# PiZeroAudio.net
KiCad netlist of a schematic drawn in EAGLE
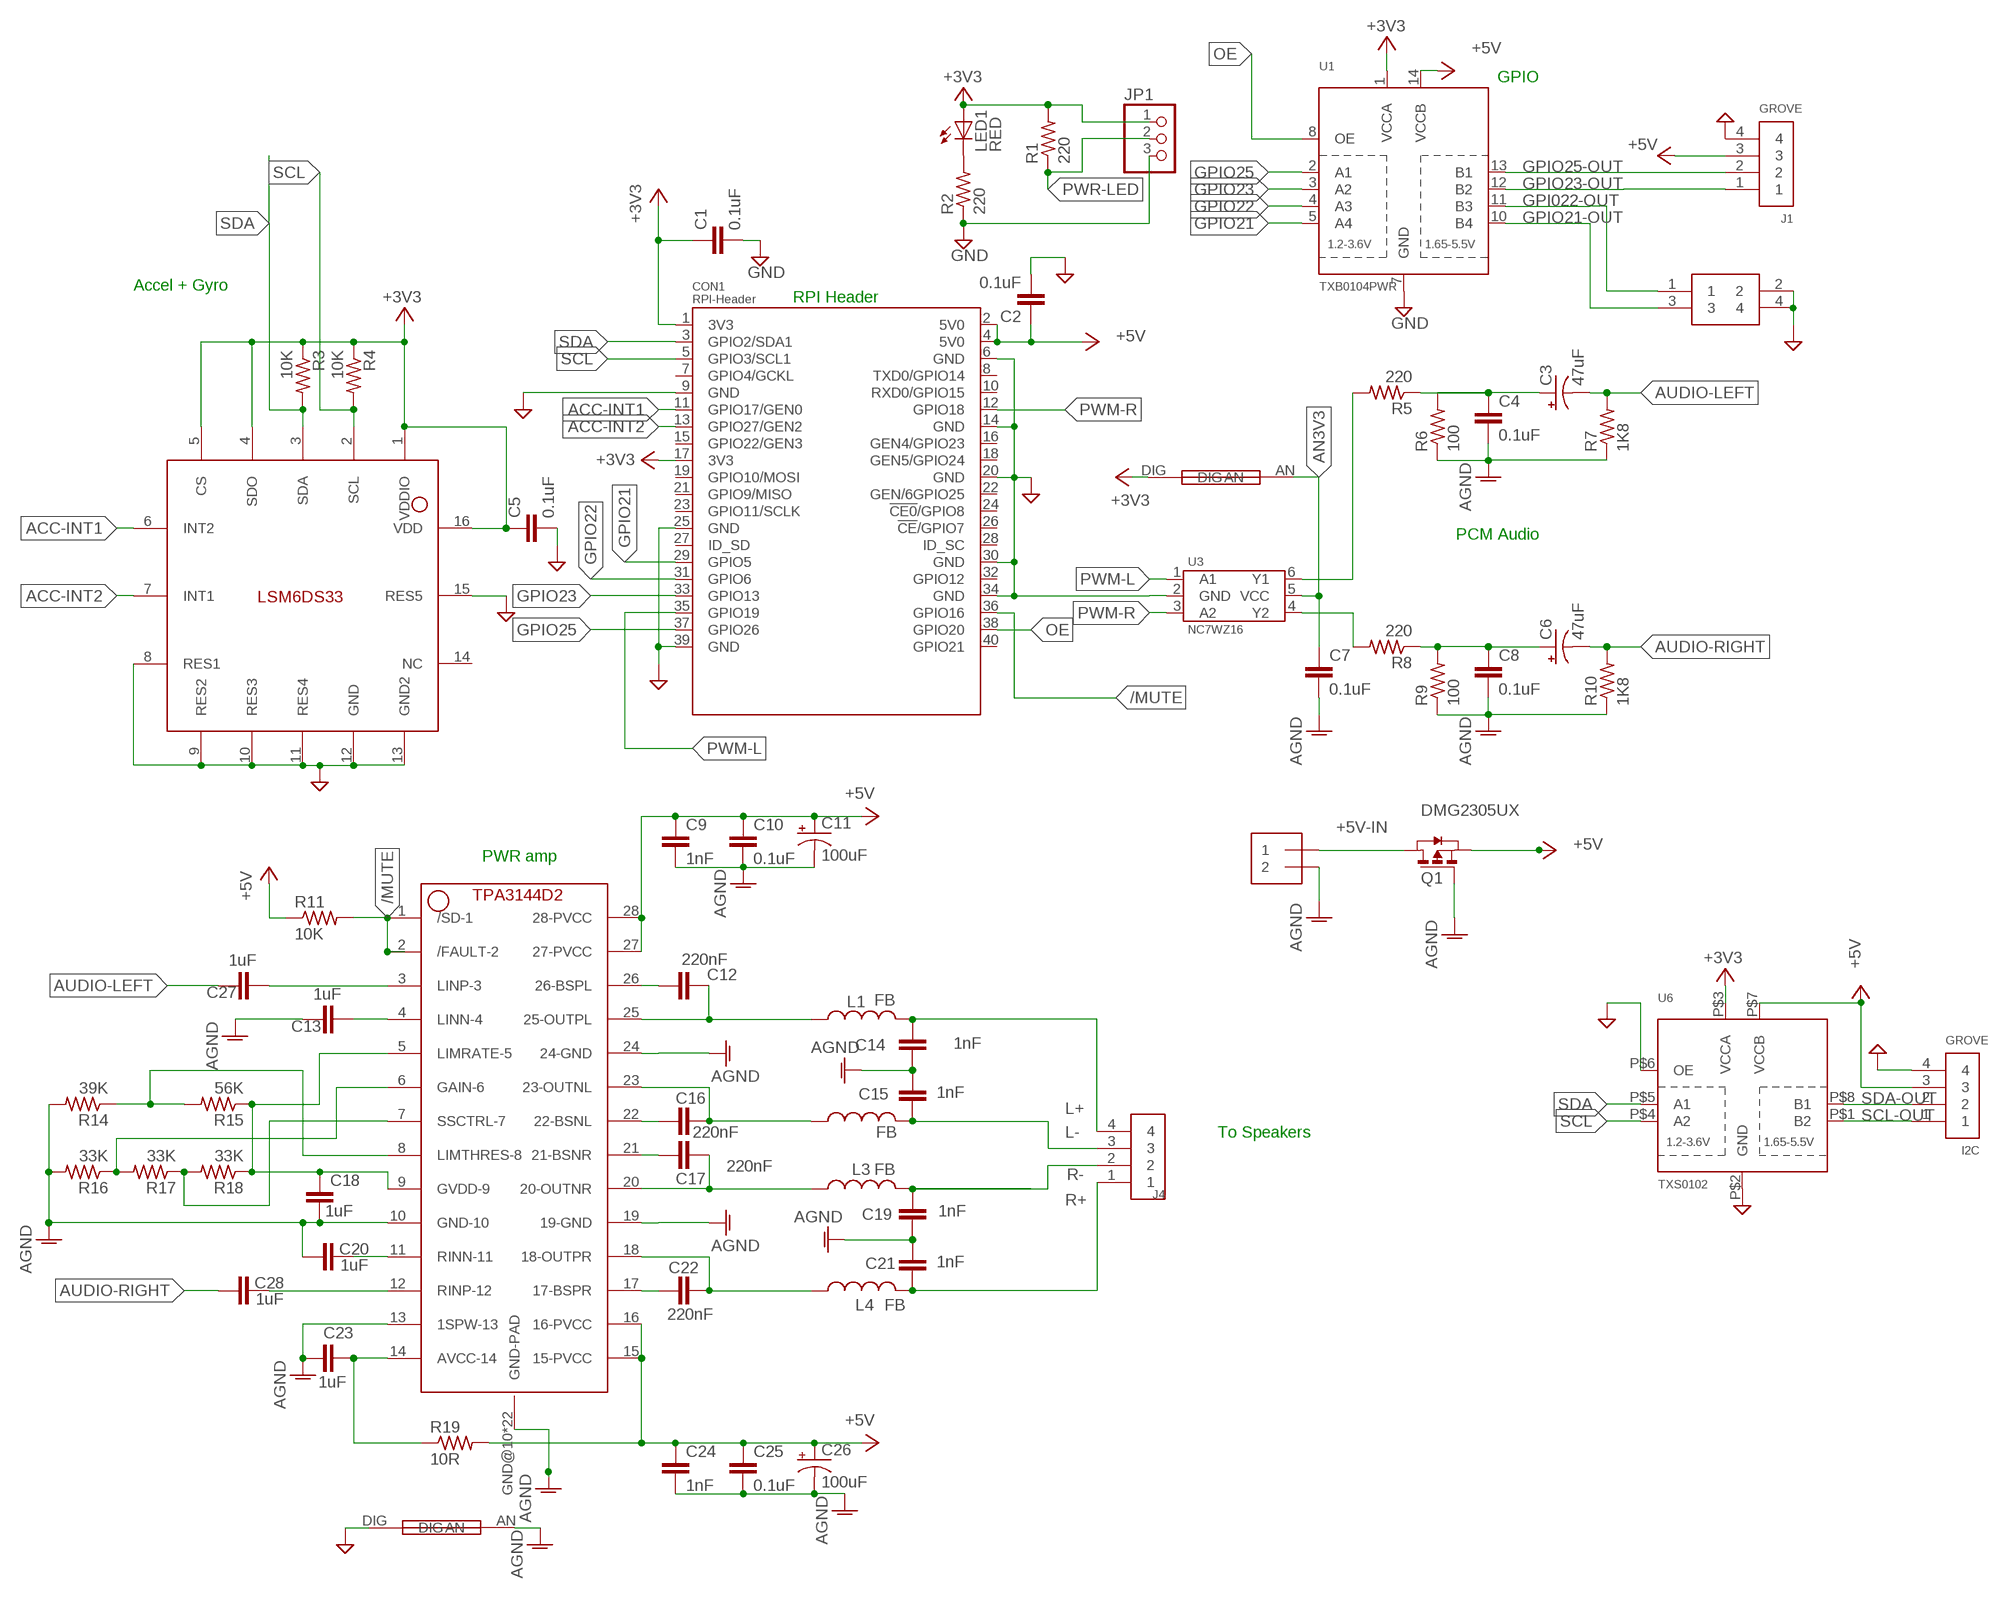
[diagram p0: schematic, sheet 1]

(export (version "E")
  (design (tool "Eeschema 10.0.6"))
  (components
    (comp (ref "C1")
      (value "0.1uF")
      (footprint "eagle-import:C0603")
      (libsource (lib "eagle-import") (part "C-EUC0603"))
    )
    (comp (ref "C2")
      (value "0.1uF")
      (footprint "eagle-import:C0603")
      (libsource (lib "eagle-import") (part "C-EUC0603"))
    )
    (comp (ref "C3")
      (value "47uF")
      (footprint "eagle-import:EIA3216")
      (libsource (lib "eagle-import") (part "CAP-POLARISED1206-POLAR"))
    )
    (comp (ref "C4")
      (value "0.1uF")
      (footprint "eagle-import:C0603")
      (libsource (lib "eagle-import") (part "C-EUC0603"))
    )
    (comp (ref "C5")
      (value "0.1uF")
      (footprint "eagle-import:C0603")
      (libsource (lib "eagle-import") (part "C-EUC0603"))
    )
    (comp (ref "C6")
      (value "47uF")
      (footprint "eagle-import:EIA3216")
      (libsource (lib "eagle-import") (part "CAP-POLARISED1206-POLAR"))
    )
    (comp (ref "C7")
      (value "0.1uF")
      (footprint "eagle-import:C0603")
      (libsource (lib "eagle-import") (part "C-EUC0603"))
    )
    (comp (ref "C8")
      (value "0.1uF")
      (footprint "eagle-import:C0603")
      (libsource (lib "eagle-import") (part "C-EUC0603"))
    )
    (comp (ref "C9")
      (value "1nF")
      (footprint "eagle-import:C0603")
      (libsource (lib "eagle-import") (part "C-EUC0603"))
    )
    (comp (ref "C10")
      (value "0.1uF")
      (footprint "eagle-import:C0603")
      (libsource (lib "eagle-import") (part "C-EUC0603"))
    )
    (comp (ref "C11")
      (value "100uF")
      (footprint "eagle-import:EIA3216")
      (libsource (lib "eagle-import") (part "CAP-POLARISED1206-POLAR"))
    )
    (comp (ref "C12")
      (value "220nF")
      (footprint "eagle-import:C0603")
      (libsource (lib "eagle-import") (part "C-EUC0603"))
    )
    (comp (ref "C13")
      (value "1uF")
      (footprint "eagle-import:C0603")
      (libsource (lib "eagle-import") (part "C-EUC0603"))
    )
    (comp (ref "C14")
      (value "1nF")
      (footprint "eagle-import:C0603")
      (libsource (lib "eagle-import") (part "C-EUC0603"))
    )
    (comp (ref "C15")
      (value "1nF")
      (footprint "eagle-import:C0603")
      (libsource (lib "eagle-import") (part "C-EUC0603"))
    )
    (comp (ref "C16")
      (value "220nF")
      (footprint "eagle-import:C0603")
      (libsource (lib "eagle-import") (part "C-EUC0603"))
    )
    (comp (ref "C17")
      (value "220nF")
      (footprint "eagle-import:C0603")
      (libsource (lib "eagle-import") (part "C-EUC0603"))
    )
    (comp (ref "C18")
      (value "1uF")
      (footprint "eagle-import:C0603")
      (libsource (lib "eagle-import") (part "C-EUC0603"))
    )
    (comp (ref "C19")
      (value "1nF")
      (footprint "eagle-import:C0603")
      (libsource (lib "eagle-import") (part "C-EUC0603"))
    )
    (comp (ref "C20")
      (value "1uF")
      (footprint "eagle-import:C0603")
      (libsource (lib "eagle-import") (part "C-EUC0603"))
    )
    (comp (ref "C21")
      (value "1nF")
      (footprint "eagle-import:C0603")
      (libsource (lib "eagle-import") (part "C-EUC0603"))
    )
    (comp (ref "C22")
      (value "220nF")
      (footprint "eagle-import:C0603")
      (libsource (lib "eagle-import") (part "C-EUC0603"))
    )
    (comp (ref "C23")
      (value "1uF")
      (footprint "eagle-import:C0603")
      (libsource (lib "eagle-import") (part "C-EUC0603"))
    )
    (comp (ref "C24")
      (value "1nF")
      (footprint "eagle-import:C0603")
      (libsource (lib "eagle-import") (part "C-EUC0603"))
    )
    (comp (ref "C25")
      (value "0.1uF")
      (footprint "eagle-import:C0603")
      (libsource (lib "eagle-import") (part "C-EUC0603"))
    )
    (comp (ref "C26")
      (value "100uF")
      (footprint "eagle-import:EIA3216")
      (libsource (lib "eagle-import") (part "CAP-POLARISED1206-POLAR"))
    )
    (comp (ref "C27")
      (value "1uF")
      (footprint "eagle-import:C0603")
      (libsource (lib "eagle-import") (part "C-EUC0603"))
    )
    (comp (ref "C28")
      (value "1uF")
      (footprint "eagle-import:C0603")
      (libsource (lib "eagle-import") (part "C-EUC0603"))
    )
    (comp (ref "CON1")
      (value "RPI-Header")
      (footprint "eagle-import:RASPBERRYPI_BASTELSTUBE_V13_RASPI_BOARD_B+_FULL")
      (libsource (lib "eagle-import") (part "RPI-ZERO"))
    )
    (comp (ref "I2C")
      (value "GROVE")
      (footprint "eagle-import:JST-PH4")
      (libsource (lib "eagle-import") (part "GROVE"))
    )
    (comp (ref "J1")
      (value "GROVE")
      (footprint "eagle-import:JST-PH4")
      (libsource (lib "eagle-import") (part "GROVE"))
    )
    (comp (ref "J2")
      (value "2X2HEADER")
      (footprint "eagle-import:2X2")
      (libsource (lib "eagle-import") (part "2X2HEADER"))
    )
    (comp (ref "J3")
      (value "2X1-LOCKING")
      (footprint "eagle-import:22-23-2021")
      (libsource (lib "eagle-import") (part "2X1-LOCKING"))
    )
    (comp (ref "J4")
      (value "4X1-LOCKING")
      (footprint "eagle-import:22-23-2041")
      (libsource (lib "eagle-import") (part "4X1-LOCKING"))
    )
    (comp (ref "JP1")
      (value "Header 1x3")
      (footprint "eagle-import:1X03")
      (libsource (lib "eagle-import") (part "PINHD-1X3"))
    )
    (comp (ref "L1")
      (value "FB")
      (footprint "eagle-import:L0806")
      (libsource (lib "eagle-import") (part "NFZ2MSML0806"))
    )
    (comp (ref "L2")
      (value "FB")
      (footprint "eagle-import:L0806")
      (libsource (lib "eagle-import") (part "NFZ2MSML0806"))
    )
    (comp (ref "L3")
      (value "FB")
      (footprint "eagle-import:L0806")
      (libsource (lib "eagle-import") (part "NFZ2MSML0806"))
    )
    (comp (ref "L4")
      (value "FB")
      (footprint "eagle-import:L0806")
      (libsource (lib "eagle-import") (part "NFZ2MSML0806"))
    )
    (comp (ref "LED1")
      (value "RED")
      (footprint "eagle-import:CHIP-LED0805")
      (libsource (lib "eagle-import") (part "LEDCHIP-LED0805"))
    )
    (comp (ref "Q1")
      (value "DMG2305UX")
      (footprint "eagle-import:SOT23")
      (libsource (lib "eagle-import") (part "DMG2305UX"))
    )
    (comp (ref "R1")
      (value "220")
      (footprint "eagle-import:R0603")
      (libsource (lib "eagle-import") (part "R-US_R0603"))
    )
    (comp (ref "R2")
      (value "220")
      (footprint "eagle-import:R0603")
      (libsource (lib "eagle-import") (part "R-US_R0603"))
    )
    (comp (ref "R3")
      (value "10K")
      (footprint "eagle-import:R0603")
      (libsource (lib "eagle-import") (part "R-US_R0603"))
    )
    (comp (ref "R4")
      (value "10K")
      (footprint "eagle-import:R0603")
      (libsource (lib "eagle-import") (part "R-US_R0603"))
    )
    (comp (ref "R5")
      (value "220")
      (footprint "eagle-import:R0603")
      (libsource (lib "eagle-import") (part "R-US_R0603"))
    )
    (comp (ref "R6")
      (value "100")
      (footprint "eagle-import:R0603")
      (libsource (lib "eagle-import") (part "R-US_R0603"))
    )
    (comp (ref "R7")
      (value "1K8")
      (footprint "eagle-import:R0603")
      (libsource (lib "eagle-import") (part "R-US_R0603"))
    )
    (comp (ref "R8")
      (value "220")
      (footprint "eagle-import:R0603")
      (libsource (lib "eagle-import") (part "R-US_R0603"))
    )
    (comp (ref "R9")
      (value "100")
      (footprint "eagle-import:R0603")
      (libsource (lib "eagle-import") (part "R-US_R0603"))
    )
    (comp (ref "R10")
      (value "1K8")
      (footprint "eagle-import:R0603")
      (libsource (lib "eagle-import") (part "R-US_R0603"))
    )
    (comp (ref "R11")
      (value "10K")
      (footprint "eagle-import:R0603")
      (libsource (lib "eagle-import") (part "R-US_R0603"))
    )
    (comp (ref "R14")
      (value "39K")
      (footprint "eagle-import:R0603")
      (libsource (lib "eagle-import") (part "R-US_R0603"))
    )
    (comp (ref "R15")
      (value "56K")
      (footprint "eagle-import:R0603")
      (libsource (lib "eagle-import") (part "R-US_R0603"))
    )
    (comp (ref "R16")
      (value "33K")
      (footprint "eagle-import:R0603")
      (libsource (lib "eagle-import") (part "R-US_R0603"))
    )
    (comp (ref "R17")
      (value "33K")
      (footprint "eagle-import:R0603")
      (libsource (lib "eagle-import") (part "R-US_R0603"))
    )
    (comp (ref "R18")
      (value "33K")
      (footprint "eagle-import:R0603")
      (libsource (lib "eagle-import") (part "R-US_R0603"))
    )
    (comp (ref "R19")
      (value "10R")
      (footprint "eagle-import:R0603")
      (libsource (lib "eagle-import") (part "R-US_R0603"))
    )
    (comp (ref "SH1")
      (value "SHORT")
      (footprint "eagle-import:SHORT")
      (libsource (lib "eagle-import") (part "SHORT"))
    )
    (comp (ref "SH2")
      (value "SHORT")
      (footprint "eagle-import:SHORT")
      (libsource (lib "eagle-import") (part "SHORT"))
    )
    (comp (ref "U1")
      (value "TXB0104PWR")
      (footprint "eagle-import:TSSOP14")
      (libsource (lib "eagle-import") (part "TXB0104PWR"))
    )
    (comp (ref "U2")
      (value "LSM6DS33")
      (footprint "eagle-import:LGA-16-3X3")
      (libsource (lib "eagle-import") (part "LSM6DS33LGA-16-3X3"))
    )
    (comp (ref "U3")
      (value "NC7WZ16")
      (footprint "eagle-import:SC-70-6")
      (libsource (lib "eagle-import") (part "NC7WZ16"))
    )
    (comp (ref "U5")
      (value "TPA3144D2PWPR")
      (footprint "eagle-import:HTSSOP28")
      (libsource (lib "eagle-import") (part "TPA3144D2PWPR"))
    )
    (comp (ref "U6")
      (value "TXS0102")
      (footprint "eagle-import:VFSOP-8")
      (libsource (lib "eagle-import") (part "TXS0102"))
    )
  )
  (nets
    (net (code "1") (name "+3V3") (class "Default")
      (node (ref "C1") (pin "1") (pinfunction "1_1") (pintype "passive"))
      (node (ref "C5") (pin "1") (pinfunction "1_1") (pintype "passive"))
      (node (ref "CON1") (pin "1") (pinfunction "3V3_1") (pintype "power_in"))
      (node (ref "CON1") (pin "17") (pinfunction "3V3_17") (pintype "power_in"))
      (node (ref "JP1") (pin "1") (pinfunction "1_1") (pintype "passive"))
      (node (ref "LED1") (pin "A") (pinfunction "A_A") (pintype "passive"))
      (node (ref "R1") (pin "2") (pinfunction "2_2") (pintype "passive"))
      (node (ref "R3") (pin "1") (pinfunction "1_1") (pintype "passive"))
      (node (ref "R4") (pin "1") (pinfunction "1_1") (pintype "passive"))
      (node (ref "SH1") (pin "DIG") (pinfunction "DIG_DIG") (pintype "bidirectional"))
      (node (ref "U1") (pin "1") (pinfunction "VCCA_1") (pintype "bidirectional"))
      (node (ref "U2") (pin "1") (pinfunction "VDDIO_1") (pintype "bidirectional"))
      (node (ref "U2") (pin "16") (pinfunction "VDD_16") (pintype "bidirectional"))
      (node (ref "U2") (pin "4") (pinfunction "SDO_4") (pintype "bidirectional"))
      (node (ref "U2") (pin "5") (pinfunction "CS_5") (pintype "bidirectional"))
      (node (ref "U6") (pin "P$3") (pinfunction "VCCA_P$3") (pintype "bidirectional"))
    )
    (net (code "2") (name "+5V") (class "Default")
      (node (ref "C10") (pin "1") (pinfunction "1_1") (pintype "passive"))
      (node (ref "C11") (pin "+") (pinfunction "+_+") (pintype "passive"))
      (node (ref "C2") (pin "1") (pinfunction "1_1") (pintype "passive"))
      (node (ref "C24") (pin "1") (pinfunction "1_1") (pintype "passive"))
      (node (ref "C25") (pin "1") (pinfunction "1_1") (pintype "passive"))
      (node (ref "C26") (pin "+") (pinfunction "+_+") (pintype "passive"))
      (node (ref "C9") (pin "1") (pinfunction "1_1") (pintype "passive"))
      (node (ref "CON1") (pin "2") (pinfunction "5V0_2") (pintype "power_in"))
      (node (ref "CON1") (pin "4") (pinfunction "5V0_4") (pintype "power_in"))
      (node (ref "I2C") (pin "3") (pinfunction "3_3") (pintype "bidirectional"))
      (node (ref "J1") (pin "3") (pinfunction "3_3") (pintype "bidirectional"))
      (node (ref "Q1") (pin "S") (pinfunction "S_S") (pintype "passive"))
      (node (ref "R11") (pin "1") (pinfunction "1_1") (pintype "passive"))
      (node (ref "R19") (pin "2") (pinfunction "2_2") (pintype "passive"))
      (node (ref "U1") (pin "14") (pinfunction "VCCB_14") (pintype "bidirectional"))
      (node (ref "U5") (pin "15") (pinfunction "15-PVCC_15") (pintype "bidirectional"))
      (node (ref "U5") (pin "16") (pinfunction "16-PVCC_16") (pintype "bidirectional"))
      (node (ref "U5") (pin "27") (pinfunction "27-PVCC_27") (pintype "bidirectional"))
      (node (ref "U5") (pin "28") (pinfunction "28-PVCC_28") (pintype "bidirectional"))
      (node (ref "U6") (pin "P$7") (pinfunction "VCCB_P$7") (pintype "bidirectional"))
    )
    (net (code "3") (name "/+5V-IN") (class "Default")
      (node (ref "J3") (pin "1") (pinfunction "1_1") (pintype "passive"))
      (node (ref "Q1") (pin "D") (pinfunction "D_D") (pintype "passive"))
    )
    (net (code "4") (name "/GPI022-OUT") (class "Default")
      (node (ref "J2") (pin "1") (pinfunction "1_1") (pintype "bidirectional"))
      (node (ref "U1") (pin "11") (pinfunction "B3_11") (pintype "bidirectional"))
    )
    (net (code "5") (name "/GPIO21-OUT") (class "Default")
      (node (ref "J2") (pin "3") (pinfunction "3_3") (pintype "bidirectional"))
      (node (ref "U1") (pin "10") (pinfunction "B4_10") (pintype "bidirectional"))
    )
    (net (code "6") (name "/GPIO23-OUT") (class "Default")
      (node (ref "J1") (pin "1") (pinfunction "1_1") (pintype "bidirectional"))
      (node (ref "U1") (pin "12") (pinfunction "B2_12") (pintype "bidirectional"))
    )
    (net (code "7") (name "/GPIO25-OUT") (class "Default")
      (node (ref "J1") (pin "2") (pinfunction "2_2") (pintype "bidirectional"))
      (node (ref "U1") (pin "13") (pinfunction "B1_13") (pintype "bidirectional"))
    )
    (net (code "8") (name "/L+") (class "Default")
      (node (ref "C14") (pin "1") (pinfunction "1_1") (pintype "passive"))
      (node (ref "J4") (pin "4") (pinfunction "4_4") (pintype "bidirectional"))
      (node (ref "L1") (pin "2") (pinfunction "2_2") (pintype "passive"))
    )
    (net (code "9") (name "/L-") (class "Default")
      (node (ref "C15") (pin "2") (pinfunction "2_2") (pintype "passive"))
      (node (ref "J4") (pin "3") (pinfunction "3_3") (pintype "bidirectional"))
      (node (ref "L2") (pin "2") (pinfunction "2_2") (pintype "passive"))
    )
    (net (code "10") (name "/R+") (class "Default")
      (node (ref "C21") (pin "2") (pinfunction "2_2") (pintype "passive"))
      (node (ref "J4") (pin "1") (pinfunction "1_1") (pintype "bidirectional"))
      (node (ref "L4") (pin "2") (pinfunction "2_2") (pintype "passive"))
    )
    (net (code "11") (name "/R-") (class "Default")
      (node (ref "C19") (pin "1") (pinfunction "1_1") (pintype "passive"))
      (node (ref "J4") (pin "2") (pinfunction "2_2") (pintype "bidirectional"))
      (node (ref "L3") (pin "2") (pinfunction "2_2") (pintype "passive"))
    )
    (net (code "12") (name "/SCL-OUT") (class "Default")
      (node (ref "I2C") (pin "1") (pinfunction "1_1") (pintype "bidirectional"))
      (node (ref "U6") (pin "P$1") (pinfunction "B2_P$1") (pintype "bidirectional"))
    )
    (net (code "13") (name "/SDA-OUT") (class "Default")
      (node (ref "I2C") (pin "2") (pinfunction "2_2") (pintype "bidirectional"))
      (node (ref "U6") (pin "P$8") (pinfunction "B1_P$8") (pintype "bidirectional"))
    )
    (net (code "14") (name "ACC-INT1") (class "Default")
      (node (ref "CON1") (pin "11") (pinfunction "GPIO17/GEN0_11") (pintype "bidirectional"))
      (node (ref "U2") (pin "6") (pinfunction "INT2_6") (pintype "bidirectional"))
    )
    (net (code "15") (name "ACC-INT2") (class "Default")
      (node (ref "CON1") (pin "13") (pinfunction "GPIO27/GEN2_13") (pintype "bidirectional"))
      (node (ref "U2") (pin "7") (pinfunction "INT1_7") (pintype "bidirectional"))
    )
    (net (code "16") (name "AGND") (class "Default")
      (node (ref "C10") (pin "2") (pinfunction "2_2") (pintype "passive"))
      (node (ref "C11") (pin "-") (pinfunction "-_-") (pintype "passive"))
      (node (ref "C13") (pin "2") (pinfunction "2_2") (pintype "passive"))
      (node (ref "C14") (pin "2") (pinfunction "2_2") (pintype "passive"))
      (node (ref "C15") (pin "1") (pinfunction "1_1") (pintype "passive"))
      (node (ref "C18") (pin "2") (pinfunction "2_2") (pintype "passive"))
      (node (ref "C19") (pin "2") (pinfunction "2_2") (pintype "passive"))
      (node (ref "C20") (pin "2") (pinfunction "2_2") (pintype "passive"))
      (node (ref "C21") (pin "1") (pinfunction "1_1") (pintype "passive"))
      (node (ref "C23") (pin "2") (pinfunction "2_2") (pintype "passive"))
      (node (ref "C24") (pin "2") (pinfunction "2_2") (pintype "passive"))
      (node (ref "C25") (pin "2") (pinfunction "2_2") (pintype "passive"))
      (node (ref "C26") (pin "-") (pinfunction "-_-") (pintype "passive"))
      (node (ref "C4") (pin "2") (pinfunction "2_2") (pintype "passive"))
      (node (ref "C7") (pin "2") (pinfunction "2_2") (pintype "passive"))
      (node (ref "C8") (pin "2") (pinfunction "2_2") (pintype "passive"))
      (node (ref "C9") (pin "2") (pinfunction "2_2") (pintype "passive"))
      (node (ref "J3") (pin "2") (pinfunction "2_2") (pintype "passive"))
      (node (ref "Q1") (pin "G") (pinfunction "G_G") (pintype "passive"))
      (node (ref "R10") (pin "1") (pinfunction "1_1") (pintype "passive"))
      (node (ref "R14") (pin "2") (pinfunction "2_2") (pintype "passive"))
      (node (ref "R16") (pin "2") (pinfunction "2_2") (pintype "passive"))
      (node (ref "R6") (pin "1") (pinfunction "1_1") (pintype "passive"))
      (node (ref "R7") (pin "1") (pinfunction "1_1") (pintype "passive"))
      (node (ref "R9") (pin "1") (pinfunction "1_1") (pintype "passive"))
      (node (ref "SH2") (pin "AN") (pinfunction "AN_AN") (pintype "bidirectional"))
      (node (ref "U5") (pin "10") (pinfunction "GND-10_10") (pintype "bidirectional"))
      (node (ref "U5") (pin "13") (pinfunction "1SPW-13_13") (pintype "bidirectional"))
      (node (ref "U5") (pin "19") (pinfunction "19-GND_19") (pintype "bidirectional"))
      (node (ref "U5") (pin "24") (pinfunction "24-GND_24") (pintype "bidirectional"))
      (node (ref "U5") (pin "GND@10") (pinfunction "GND-PAD_GND@10") (pintype "bidirectional"))
      (node (ref "U5") (pin "GND@11") (pinfunction "GND-PAD_GND@11") (pintype "bidirectional"))
      (node (ref "U5") (pin "GND@12") (pinfunction "GND-PAD_GND@12") (pintype "bidirectional"))
      (node (ref "U5") (pin "GND@13") (pinfunction "GND-PAD_GND@13") (pintype "bidirectional"))
      (node (ref "U5") (pin "GND@14") (pinfunction "GND-PAD_GND@14") (pintype "bidirectional"))
      (node (ref "U5") (pin "GND@15") (pinfunction "GND-PAD_GND@15") (pintype "bidirectional"))
      (node (ref "U5") (pin "GND@16") (pinfunction "GND-PAD_GND@16") (pintype "bidirectional"))
      (node (ref "U5") (pin "GND@17") (pinfunction "GND-PAD_GND@17") (pintype "bidirectional"))
      (node (ref "U5") (pin "GND@18") (pinfunction "GND-PAD_GND@18") (pintype "bidirectional"))
      (node (ref "U5") (pin "GND@19") (pinfunction "GND-PAD_GND@19") (pintype "bidirectional"))
      (node (ref "U5") (pin "GND@20") (pinfunction "GND-PAD_GND@20") (pintype "bidirectional"))
      (node (ref "U5") (pin "GND@21") (pinfunction "GND-PAD_GND@21") (pintype "bidirectional"))
      (node (ref "U5") (pin "GND@22") (pinfunction "GND-PAD_GND@22") (pintype "bidirectional"))
      (node (ref "U5") (pin "GND@23") (pinfunction "GND-PAD_GND@23") (pintype "bidirectional"))
      (node (ref "U5") (pin "GND@24") (pinfunction "GND-PAD_GND@24") (pintype "bidirectional"))
      (node (ref "U5") (pin "GND@25") (pinfunction "GND-PAD_GND@25") (pintype "bidirectional"))
      (node (ref "U5") (pin "GND@26") (pinfunction "GND-PAD_GND@26") (pintype "bidirectional"))
      (node (ref "U5") (pin "GND@27") (pinfunction "GND-PAD_GND@27") (pintype "bidirectional"))
      (node (ref "U5") (pin "GND@28") (pinfunction "GND-PAD_GND@28") (pintype "bidirectional"))
      (node (ref "U5") (pin "GND@29") (pinfunction "GND-PAD_GND@29") (pintype "bidirectional"))
      (node (ref "U5") (pin "GND@30") (pinfunction "GND-PAD_GND@30") (pintype "bidirectional"))
      (node (ref "U5") (pin "GND@PAD") (pinfunction "GND-PAD_GND@PAD") (pintype "bidirectional"))
    )
    (net (code "17") (name "AN3V3") (class "Default")
      (node (ref "C7") (pin "1") (pinfunction "1_1") (pintype "passive"))
      (node (ref "SH1") (pin "AN") (pinfunction "AN_AN") (pintype "bidirectional"))
      (node (ref "U3") (pin "5") (pinfunction "VCC_5") (pintype "bidirectional"))
    )
    (net (code "18") (name "AUDIO-LEFT") (class "Default")
      (node (ref "C27") (pin "2") (pinfunction "2_2") (pintype "passive"))
      (node (ref "C3") (pin "-") (pinfunction "-_-") (pintype "passive"))
      (node (ref "R7") (pin "2") (pinfunction "2_2") (pintype "passive"))
    )
    (net (code "19") (name "AUDIO-RIGHT") (class "Default")
      (node (ref "C28") (pin "2") (pinfunction "2_2") (pintype "passive"))
      (node (ref "C6") (pin "-") (pinfunction "-_-") (pintype "passive"))
      (node (ref "R10") (pin "2") (pinfunction "2_2") (pintype "passive"))
    )
    (net (code "20") (name "GND") (class "Default")
      (node (ref "C1") (pin "2") (pinfunction "2_2") (pintype "passive"))
      (node (ref "C2") (pin "2") (pinfunction "2_2") (pintype "passive"))
      (node (ref "C5") (pin "2") (pinfunction "2_2") (pintype "passive"))
      (node (ref "CON1") (pin "14") (pinfunction "GND_14") (pintype "power_in"))
      (node (ref "CON1") (pin "20") (pinfunction "GND_20") (pintype "power_in"))
      (node (ref "CON1") (pin "25") (pinfunction "GND_25") (pintype "power_in"))
      (node (ref "CON1") (pin "30") (pinfunction "GND_30") (pintype "power_in"))
      (node (ref "CON1") (pin "34") (pinfunction "GND_34") (pintype "power_in"))
      (node (ref "CON1") (pin "39") (pinfunction "GND_39") (pintype "power_in"))
      (node (ref "CON1") (pin "6") (pinfunction "GND_6") (pintype "power_in"))
      (node (ref "CON1") (pin "9") (pinfunction "GND_9") (pintype "power_in"))
      (node (ref "I2C") (pin "4") (pinfunction "4_4") (pintype "bidirectional"))
      (node (ref "J1") (pin "4") (pinfunction "4_4") (pintype "bidirectional"))
      (node (ref "J2") (pin "2") (pinfunction "2_2") (pintype "bidirectional"))
      (node (ref "J2") (pin "4") (pinfunction "4_4") (pintype "bidirectional"))
      (node (ref "JP1") (pin "3") (pinfunction "3_3") (pintype "passive"))
      (node (ref "R2") (pin "1") (pinfunction "1_1") (pintype "passive"))
      (node (ref "SH2") (pin "DIG") (pinfunction "DIG_DIG") (pintype "bidirectional"))
      (node (ref "U1") (pin "7") (pinfunction "GND_7") (pintype "bidirectional"))
      (node (ref "U2") (pin "10") (pinfunction "RES3_10") (pintype "bidirectional"))
      (node (ref "U2") (pin "11") (pinfunction "RES4_11") (pintype "bidirectional"))
      (node (ref "U2") (pin "12") (pinfunction "GND_12") (pintype "bidirectional"))
      (node (ref "U2") (pin "13") (pinfunction "GND2_13") (pintype "bidirectional"))
      (node (ref "U2") (pin "15") (pinfunction "RES5_15") (pintype "bidirectional"))
      (node (ref "U2") (pin "8") (pinfunction "RES1_8") (pintype "bidirectional"))
      (node (ref "U2") (pin "9") (pinfunction "RES2_9") (pintype "bidirectional"))
      (node (ref "U3") (pin "2") (pinfunction "GND_2") (pintype "bidirectional"))
      (node (ref "U6") (pin "P$2") (pinfunction "GND_P$2") (pintype "bidirectional"))
      (node (ref "U6") (pin "P$6") (pinfunction "OE_P$6") (pintype "bidirectional"))
    )
    (net (code "21") (name "GPIO21") (class "Default")
      (node (ref "CON1") (pin "29") (pinfunction "GPIO5_29") (pintype "bidirectional"))
      (node (ref "U1") (pin "5") (pinfunction "A4_5") (pintype "bidirectional"))
    )
    (net (code "22") (name "GPIO22") (class "Default")
      (node (ref "CON1") (pin "31") (pinfunction "GPIO6_31") (pintype "bidirectional"))
      (node (ref "U1") (pin "4") (pinfunction "A3_4") (pintype "bidirectional"))
    )
    (net (code "23") (name "GPIO23") (class "Default")
      (node (ref "CON1") (pin "33") (pinfunction "GPIO13_33") (pintype "bidirectional"))
      (node (ref "U1") (pin "3") (pinfunction "A2_3") (pintype "bidirectional"))
    )
    (net (code "24") (name "GPIO25") (class "Default")
      (node (ref "CON1") (pin "37") (pinfunction "GPIO26_37") (pintype "bidirectional"))
      (node (ref "U1") (pin "2") (pinfunction "A1_2") (pintype "bidirectional"))
    )
    (net (code "25") (name "Net-(C3-Pad+)") (class "Default")
      (node (ref "C3") (pin "+") (pinfunction "+_+") (pintype "passive"))
      (node (ref "C4") (pin "1") (pinfunction "1_1") (pintype "passive"))
      (node (ref "R5") (pin "1") (pinfunction "1_1") (pintype "passive"))
      (node (ref "R6") (pin "2") (pinfunction "2_2") (pintype "passive"))
    )
    (net (code "26") (name "Net-(C6-Pad+)") (class "Default")
      (node (ref "C6") (pin "+") (pinfunction "+_+") (pintype "passive"))
      (node (ref "C8") (pin "1") (pinfunction "1_1") (pintype "passive"))
      (node (ref "R8") (pin "1") (pinfunction "1_1") (pintype "passive"))
      (node (ref "R9") (pin "2") (pinfunction "2_2") (pintype "passive"))
    )
    (net (code "27") (name "Net-(LED1-PadC)") (class "Default")
      (node (ref "LED1") (pin "C") (pinfunction "C_C") (pintype "passive"))
      (node (ref "R2") (pin "2") (pinfunction "2_2") (pintype "passive"))
    )
    (net (code "28") (name "Net-(U3-Y1)") (class "Default")
      (node (ref "R5") (pin "2") (pinfunction "2_2") (pintype "passive"))
      (node (ref "U3") (pin "6") (pinfunction "Y1_6") (pintype "bidirectional"))
    )
    (net (code "29") (name "Net-(U3-Y2)") (class "Default")
      (node (ref "R8") (pin "2") (pinfunction "2_2") (pintype "passive"))
      (node (ref "U3") (pin "4") (pinfunction "Y2_4") (pintype "bidirectional"))
    )
    (net (code "30") (name "Net-(U5-17-BSPR)") (class "Default")
      (node (ref "C22") (pin "2") (pinfunction "2_2") (pintype "passive"))
      (node (ref "U5") (pin "17") (pinfunction "17-BSPR_17") (pintype "bidirectional"))
    )
    (net (code "31") (name "Net-(U5-18-OUTPR)") (class "Default")
      (node (ref "C22") (pin "1") (pinfunction "1_1") (pintype "passive"))
      (node (ref "L4") (pin "1") (pinfunction "1_1") (pintype "passive"))
      (node (ref "U5") (pin "18") (pinfunction "18-OUTPR_18") (pintype "bidirectional"))
    )
    (net (code "32") (name "Net-(U5-20-OUTNR)") (class "Default")
      (node (ref "C17") (pin "1") (pinfunction "1_1") (pintype "passive"))
      (node (ref "L3") (pin "1") (pinfunction "1_1") (pintype "passive"))
      (node (ref "U5") (pin "20") (pinfunction "20-OUTNR_20") (pintype "bidirectional"))
    )
    (net (code "33") (name "Net-(U5-21-BSNR)") (class "Default")
      (node (ref "C17") (pin "2") (pinfunction "2_2") (pintype "passive"))
      (node (ref "U5") (pin "21") (pinfunction "21-BSNR_21") (pintype "bidirectional"))
    )
    (net (code "34") (name "Net-(U5-22-BSNL)") (class "Default")
      (node (ref "C16") (pin "2") (pinfunction "2_2") (pintype "passive"))
      (node (ref "U5") (pin "22") (pinfunction "22-BSNL_22") (pintype "bidirectional"))
    )
    (net (code "35") (name "Net-(U5-23-OUTNL)") (class "Default")
      (node (ref "C16") (pin "1") (pinfunction "1_1") (pintype "passive"))
      (node (ref "L2") (pin "1") (pinfunction "1_1") (pintype "passive"))
      (node (ref "U5") (pin "23") (pinfunction "23-OUTNL_23") (pintype "bidirectional"))
    )
    (net (code "36") (name "Net-(U5-25-OUTPL)") (class "Default")
      (node (ref "C12") (pin "1") (pinfunction "1_1") (pintype "passive"))
      (node (ref "L1") (pin "1") (pinfunction "1_1") (pintype "passive"))
      (node (ref "U5") (pin "25") (pinfunction "25-OUTPL_25") (pintype "bidirectional"))
    )
    (net (code "37") (name "Net-(U5-26-BSPL)") (class "Default")
      (node (ref "C12") (pin "2") (pinfunction "2_2") (pintype "passive"))
      (node (ref "U5") (pin "26") (pinfunction "26-BSPL_26") (pintype "bidirectional"))
    )
    (net (code "38") (name "Net-(U5-AVCC-14)") (class "Default")
      (node (ref "C23") (pin "1") (pinfunction "1_1") (pintype "passive"))
      (node (ref "R19") (pin "1") (pinfunction "1_1") (pintype "passive"))
      (node (ref "U5") (pin "14") (pinfunction "AVCC-14_14") (pintype "bidirectional"))
    )
    (net (code "39") (name "Net-(U5-GAIN-6)") (class "Default")
      (node (ref "R16") (pin "1") (pinfunction "1_1") (pintype "passive"))
      (node (ref "R17") (pin "2") (pinfunction "2_2") (pintype "passive"))
      (node (ref "U5") (pin "6") (pinfunction "GAIN-6_6") (pintype "bidirectional"))
    )
    (net (code "40") (name "Net-(U5-GVDD-9)") (class "Default")
      (node (ref "C18") (pin "1") (pinfunction "1_1") (pintype "passive"))
      (node (ref "R15") (pin "1") (pinfunction "1_1") (pintype "passive"))
      (node (ref "R18") (pin "1") (pinfunction "1_1") (pintype "passive"))
      (node (ref "U5") (pin "5") (pinfunction "LIMRATE-5_5") (pintype "bidirectional"))
      (node (ref "U5") (pin "9") (pinfunction "GVDD-9_9") (pintype "bidirectional"))
    )
    (net (code "41") (name "Net-(U5-LIMTHRES-8)") (class "Default")
      (node (ref "R14") (pin "1") (pinfunction "1_1") (pintype "passive"))
      (node (ref "R15") (pin "2") (pinfunction "2_2") (pintype "passive"))
      (node (ref "U5") (pin "8") (pinfunction "LIMTHRES-8_8") (pintype "bidirectional"))
    )
    (net (code "42") (name "Net-(U5-LINN-4)") (class "Default")
      (node (ref "C13") (pin "1") (pinfunction "1_1") (pintype "passive"))
      (node (ref "U5") (pin "4") (pinfunction "LINN-4_4") (pintype "bidirectional"))
    )
    (net (code "43") (name "Net-(U5-LINP-3)") (class "Default")
      (node (ref "C27") (pin "1") (pinfunction "1_1") (pintype "passive"))
      (node (ref "U5") (pin "3") (pinfunction "LINP-3_3") (pintype "bidirectional"))
    )
    (net (code "44") (name "Net-(U5-RINN-11)") (class "Default")
      (node (ref "C20") (pin "1") (pinfunction "1_1") (pintype "passive"))
      (node (ref "U5") (pin "11") (pinfunction "RINN-11_11") (pintype "bidirectional"))
    )
    (net (code "45") (name "Net-(U5-RINP-12)") (class "Default")
      (node (ref "C28") (pin "1") (pinfunction "1_1") (pintype "passive"))
      (node (ref "U5") (pin "12") (pinfunction "RINP-12_12") (pintype "bidirectional"))
    )
    (net (code "46") (name "Net-(U5-SSCTRL-7)") (class "Default")
      (node (ref "R17") (pin "1") (pinfunction "1_1") (pintype "passive"))
      (node (ref "R18") (pin "2") (pinfunction "2_2") (pintype "passive"))
      (node (ref "U5") (pin "7") (pinfunction "SSCTRL-7_7") (pintype "bidirectional"))
    )
    (net (code "47") (name "OE") (class "Default")
      (node (ref "CON1") (pin "38") (pinfunction "GPIO20_38") (pintype "bidirectional"))
      (node (ref "U1") (pin "8") (pinfunction "OE_8") (pintype "bidirectional"))
    )
    (net (code "48") (name "PWM-L") (class "Default")
      (node (ref "CON1") (pin "35") (pinfunction "GPIO19_35") (pintype "bidirectional"))
      (node (ref "U3") (pin "1") (pinfunction "A1_1") (pintype "bidirectional"))
    )
    (net (code "49") (name "PWM-R") (class "Default")
      (node (ref "CON1") (pin "12") (pinfunction "GPIO18_12") (pintype "bidirectional"))
      (node (ref "U3") (pin "3") (pinfunction "A2_3") (pintype "bidirectional"))
    )
    (net (code "50") (name "PWR-LED") (class "Default")
      (node (ref "JP1") (pin "2") (pinfunction "2_2") (pintype "passive"))
      (node (ref "R1") (pin "1") (pinfunction "1_1") (pintype "passive"))
    )
    (net (code "51") (name "SCL") (class "Default")
      (node (ref "CON1") (pin "5") (pinfunction "GPIO3/SCL1_5") (pintype "bidirectional"))
      (node (ref "R4") (pin "2") (pinfunction "2_2") (pintype "passive"))
      (node (ref "U2") (pin "2") (pinfunction "SCL_2") (pintype "bidirectional"))
      (node (ref "U6") (pin "P$4") (pinfunction "A2_P$4") (pintype "bidirectional"))
    )
    (net (code "52") (name "SDA") (class "Default")
      (node (ref "CON1") (pin "3") (pinfunction "GPIO2/SDA1_3") (pintype "bidirectional"))
      (node (ref "R3") (pin "2") (pinfunction "2_2") (pintype "passive"))
      (node (ref "U2") (pin "3") (pinfunction "SDA_3") (pintype "bidirectional"))
      (node (ref "U6") (pin "P$5") (pinfunction "A1_P$5") (pintype "bidirectional"))
    )
    (net (code "53") (name "unconnected-(CON1-GEN4{slash}GPIO23-Pad16)") (class "Default")
      (node (ref "CON1") (pin "16") (pinfunction "GEN4/GPIO23_16") (pintype "bidirectional"))
    )
    (net (code "54") (name "unconnected-(CON1-GEN5{slash}GPIO24-Pad18)") (class "Default")
      (node (ref "CON1") (pin "18") (pinfunction "GEN5/GPIO24_18") (pintype "bidirectional"))
    )
    (net (code "55") (name "unconnected-(CON1-GEN{slash}6GPIO25-Pad22)") (class "Default")
      (node (ref "CON1") (pin "22") (pinfunction "GEN/6GPIO25_22") (pintype "bidirectional"))
    )
    (net (code "56") (name "unconnected-(CON1-GPIO4{slash}GCKL-Pad7)") (class "Default")
      (node (ref "CON1") (pin "7") (pinfunction "GPIO4/GCKL_7") (pintype "bidirectional"))
    )
    (net (code "57") (name "unconnected-(CON1-GPIO9{slash}MISO-Pad21)") (class "Default")
      (node (ref "CON1") (pin "21") (pinfunction "GPIO9/MISO_21") (pintype "bidirectional"))
    )
    (net (code "58") (name "unconnected-(CON1-GPIO10{slash}MOSI-Pad19)") (class "Default")
      (node (ref "CON1") (pin "19") (pinfunction "GPIO10/MOSI_19") (pintype "bidirectional"))
    )
    (net (code "59") (name "unconnected-(CON1-GPIO11{slash}SCLK-Pad23)") (class "Default")
      (node (ref "CON1") (pin "23") (pinfunction "GPIO11/SCLK_23") (pintype "bidirectional"))
    )
    (net (code "60") (name "unconnected-(CON1-GPIO12-Pad32)") (class "Default")
      (node (ref "CON1") (pin "32") (pinfunction "GPIO12_32") (pintype "bidirectional"))
    )
    (net (code "61") (name "unconnected-(CON1-GPIO21-Pad40)") (class "Default")
      (node (ref "CON1") (pin "40") (pinfunction "GPIO21_40") (pintype "bidirectional"))
    )
    (net (code "62") (name "unconnected-(CON1-GPIO22{slash}GEN3-Pad15)") (class "Default")
      (node (ref "CON1") (pin "15") (pinfunction "GPIO22/GEN3_15") (pintype "bidirectional"))
    )
    (net (code "63") (name "unconnected-(CON1-ID_SC-Pad28)") (class "Default")
      (node (ref "CON1") (pin "28") (pinfunction "ID_SC_28") (pintype "bidirectional"))
    )
    (net (code "64") (name "unconnected-(CON1-ID_SD-Pad27)") (class "Default")
      (node (ref "CON1") (pin "27") (pinfunction "ID_SD_27") (pintype "bidirectional"))
    )
    (net (code "65") (name "unconnected-(CON1-RXD0{slash}GPIO15-Pad10)") (class "Default")
      (node (ref "CON1") (pin "10") (pinfunction "RXD0/GPIO15_10") (pintype "bidirectional"))
    )
    (net (code "66") (name "unconnected-(CON1-TXD0{slash}GPIO14-Pad8)") (class "Default")
      (node (ref "CON1") (pin "8") (pinfunction "TXD0/GPIO14_8") (pintype "bidirectional"))
    )
    (net (code "67") (name "unconnected-(CON1-~{CE0}{slash}GPIO8-Pad24)") (class "Default")
      (node (ref "CON1") (pin "24") (pinfunction "~{CE0}/GPIO8_24") (pintype "bidirectional"))
    )
    (net (code "68") (name "unconnected-(CON1-~{CE}{slash}GPIO7-Pad26)") (class "Default")
      (node (ref "CON1") (pin "26") (pinfunction "~{CE}/GPIO7_26") (pintype "bidirectional"))
    )
    (net (code "69") (name "unconnected-(U2-NC-Pad14)") (class "Default")
      (node (ref "U2") (pin "14") (pinfunction "NC_14") (pintype "bidirectional"))
    )
    (net (code "70") (name "{slash}MUTE") (class "Default")
      (node (ref "CON1") (pin "36") (pinfunction "GPIO16_36") (pintype "bidirectional"))
      (node (ref "R11") (pin "2") (pinfunction "2_2") (pintype "passive"))
      (node (ref "U5") (pin "1") (pinfunction "/SD-1_1") (pintype "bidirectional"))
      (node (ref "U5") (pin "2") (pinfunction "/FAULT-2_2") (pintype "bidirectional"))
    )
  )
)
